# Radio.net
KiCad netlist of a schematic drawn in Altium Designer
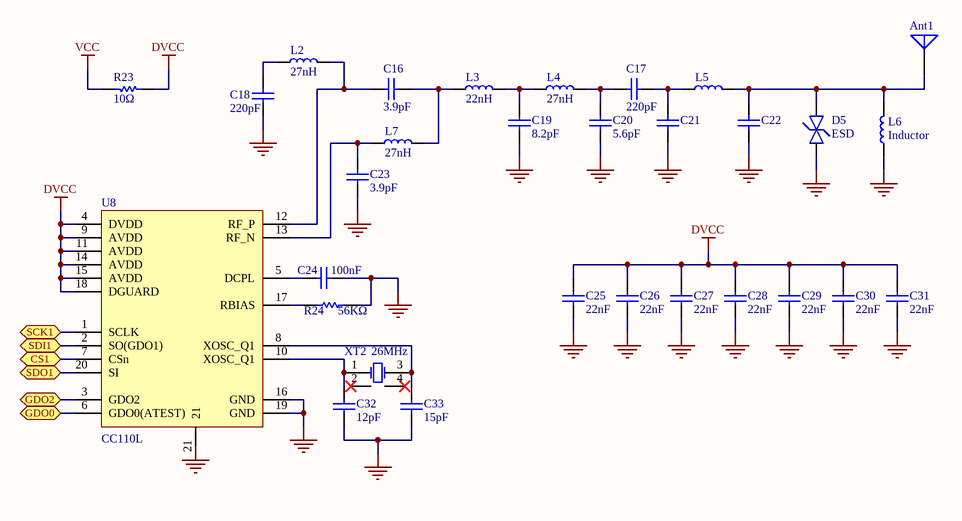
[diagram p0: Radio.SchDoc]

(export (version "E")
  (design (tool "Eeschema 10.0.6"))
  (components
    (comp (ref "Ant1")
      (value "Antenna")
      (footprint "35 mil hole")
      (description "6.8\" Whip Antenna")
      (fields (field (name "MANUFACTURER") "Alpha Wire"))
      (libsource (lib "Miscellaneous Devices") (part "Antenna"))
    )
    (comp (ref "C16")
      (value "3.9pF")
      (footprint "0402 Small")
      (description "Capacitor, 3.9p, 0402, NP0, +-0.25pF, 50V")
      (fields (field (name "MANUFACTURER") "MURATA ELECTRONICS"))
      (libsource (lib "Miscellaneous Devices") (part "Cap"))
    )
    (comp (ref "C17")
      (value "220pF")
      (footprint "0402 Small")
      (description "Capacitor, 220p, 0402, NP0, 5%, 50V")
      (fields (field (name "MANUFACTURER") "MURATA ELECTRONICS"))
      (libsource (lib "Miscellaneous Devices") (part "Cap"))
    )
    (comp (ref "C18")
      (value "220pF")
      (footprint "0402 Small")
      (description "Capacitor, 220p, 0402, NP0, 5%, 50V")
      (fields (field (name "MANUFACTURER") "MURATA ELECTRONICS"))
      (libsource (lib "Miscellaneous Devices") (part "Cap"))
    )
    (comp (ref "C19")
      (value "8.2pF")
      (footprint "0402 Small")
      (description "Capacitor, 8.2p, 0402, NP0, +-0.25pF, 50V")
      (fields (field (name "MANUFACTURER") "MURATA ELECTRONICS"))
      (libsource (lib "Miscellaneous Devices") (part "Cap"))
    )
    (comp (ref "C20")
      (value "5.6pF")
      (footprint "0402 Small")
      (description "Capacitor, 5.6p, 0402, NP0, +-0.25pF, 50V")
      (fields (field (name "MANUFACTURER") "MURATA ELECTRONICS"))
      (libsource (lib "Miscellaneous Devices") (part "Cap"))
    )
    (comp (ref "C21")
      (value "NP")
      (footprint "0402 Small")
      (libsource (lib "Miscellaneous Devices") (part "Cap"))
    )
    (comp (ref "C22")
      (value "NP")
      (footprint "0402 Small")
      (libsource (lib "Miscellaneous Devices") (part "Cap"))
    )
    (comp (ref "C23")
      (value "3.9pF")
      (footprint "0402 Small")
      (description "Capacitor, 3.9p, 0402, NP0, +-0.25pF, 50V")
      (fields (field (name "MANUFACTURER") "MURATA ELECTRONICS"))
      (libsource (lib "Miscellaneous Devices") (part "Cap"))
    )
    (comp (ref "C24")
      (value "100nF")
      (footprint "0402 Small")
      (description "Capacitor, 100n, 0402, X5R, 10%, 10V")
      (fields (field (name "MANUFACTURER") "MURATA ELECTRONICS"))
      (libsource (lib "Miscellaneous Devices") (part "Cap"))
    )
    (comp (ref "C25")
      (value "22nF")
      (footprint "0402 Small")
      (description "Capacitor, 22n, 0402, X7R, 10%, 25V")
      (fields (field (name "MANUFACTURER") "MURATA ELECTRONICS"))
      (libsource (lib "Miscellaneous Devices") (part "Cap"))
    )
    (comp (ref "C26")
      (value "22nF")
      (footprint "0402 Small")
      (description "Capacitor, 22n, 0402, X7R, 10%, 25V")
      (fields (field (name "MANUFACTURER") "MURATA ELECTRONICS"))
      (libsource (lib "Miscellaneous Devices") (part "Cap"))
    )
    (comp (ref "C27")
      (value "22nF")
      (footprint "0402 Small")
      (description "Capacitor, 22n, 0402, X7R, 10%, 25V")
      (fields (field (name "MANUFACTURER") "MURATA ELECTRONICS"))
      (libsource (lib "Miscellaneous Devices") (part "Cap"))
    )
    (comp (ref "C28")
      (value "22nF")
      (footprint "0402 Small")
      (description "Capacitor, 22n, 0402, X7R, 10%, 25V")
      (fields (field (name "MANUFACTURER") "MURATA ELECTRONICS"))
      (libsource (lib "Miscellaneous Devices") (part "Cap"))
    )
    (comp (ref "C29")
      (value "22nF")
      (footprint "0402 Small")
      (description "Capacitor, 22n, 0402, X7R, 10%, 25V")
      (fields (field (name "MANUFACTURER") "MURATA ELECTRONICS"))
      (libsource (lib "Miscellaneous Devices") (part "Cap"))
    )
    (comp (ref "C30")
      (value "22nF")
      (footprint "0402 Small")
      (description "Capacitor, 22n, 0402, X7R, 10%, 25V")
      (fields (field (name "MANUFACTURER") "MURATA ELECTRONICS"))
      (libsource (lib "Miscellaneous Devices") (part "Cap"))
    )
    (comp (ref "C31")
      (value "22nF")
      (footprint "0402 Small")
      (description "Capacitor, 22n, 0402, X7R, 10%, 25V")
      (fields (field (name "MANUFACTURER") "MURATA ELECTRONICS"))
      (libsource (lib "Miscellaneous Devices") (part "Cap"))
    )
    (comp (ref "C32")
      (value "12pF")
      (footprint "0402 Small")
      (description "CAP CER 12PF 50V 5% NP0 0402")
      (fields (field (name "MANUFACTURER") "MURATA ELECTRONICS"))
      (libsource (lib "Miscellaneous Devices") (part "Cap"))
    )
    (comp (ref "C33")
      (value "15pF")
      (footprint "0402 Small")
      (description "CAP CER 15PF 50V 5% NP0 0402")
      (fields (field (name "MANUFACTURER") "MURATA ELECTRONICS"))
      (libsource (lib "Miscellaneous Devices") (part "Cap"))
    )
    (comp (ref "D5")
      (value "ESD")
      (footprint "XDFN2")
      (description "TVS DIODE 16VWM 39VC 2XDFN")
      (fields (field (name "MANUFACTURER") "ON Semiconductor"))
      (libsource (lib "Curtis") (part "BiDi"))
    )
    (comp (ref "L2")
      (value "27nH")
      (footprint "0402 Small")
      (description "Inductor, 27n, 0402, ±5%")
      (fields (field (name "MANUFACTURER") "MURATA ELECTRONICS"))
      (libsource (lib "Curtis") (part "Inductor"))
    )
    (comp (ref "L3")
      (value "22nH")
      (footprint "0402 Small")
      (description "Inductor, 22n, 0402, ±5%")
      (fields (field (name "MANUFACTURER") "MURATA ELECTRONICS"))
      (libsource (lib "Curtis") (part "Inductor"))
    )
    (comp (ref "L4")
      (value "27nH")
      (footprint "0402 Small")
      (description "Inductor, 27n, 0402, ±5%")
      (fields (field (name "MANUFACTURER") "MURATA ELECTRONICS"))
      (libsource (lib "Curtis") (part "Inductor"))
    )
    (comp (ref "L5") (value "NP") (footprint "0402 Small") (libsource (lib "Curtis") (part "Inductor")))
    (comp (ref "L6")
      (value "Inductor")
      (footprint "0402 Small")
      (description "Fixed Inductors 0.68uH")
      (fields (field (name "MANUFACTURER") "TDK"))
      (libsource (lib "Curtis") (part "Inductor"))
    )
    (comp (ref "L7")
      (value "27nH")
      (footprint "0402 Small")
      (description "Inductor, 27n, 0402, ±5%")
      (fields (field (name "MANUFACTURER") "MURATA ELECTRONICS"))
      (libsource (lib "Curtis") (part "Inductor"))
    )
    (comp (ref "R23")
      (value "10Ω")
      (footprint "0603 Small")
      (description "Thick Film Resistors - SMD 1/10watt 10ohms 1%")
      (fields (field (name "MANUFACTURER") "Vishay Semiconductors"))
      (libsource (lib "Miscellaneous Devices") (part "Res1"))
    )
    (comp (ref "R24")
      (value "56KΩ")
      (footprint "0402 Small")
      (description "Resistor, 56k ohms, 0402,  ±1%")
      (fields (field (name "MANUFACTURER") "Koa"))
      (libsource (lib "Miscellaneous Devices") (part "Res1"))
    )
    (comp (ref "U8")
      (value "CC110L")
      (footprint "VQFN-20")
      (description "IC RF VALUE LINE TXRX 20QFN")
      (fields (field (name "MANUFACTURER") "Texas Instruments"))
      (libsource (lib "OrangeBox") (part "CC1101"))
    )
    (comp (ref "XT2")
      (value "26MHz")
      (footprint "CFPX-5")
      (description "CRYSTAL 26MHZ 10PF SMD")
      (fields (field (name "MANUFACTURER") "Suntsu"))
      (libsource (lib "Altium Design Library") (part "CRYS"))
    )
  )
  (nets
    (net (code "1") (name "/CS1") (class "Default")
      (node (ref "U8") (pin "7") (pinfunction "CSn_7") (pintype "passive"))
    )
    (net (code "2") (name "/GDO0") (class "Default")
      (node (ref "U8") (pin "6") (pinfunction "GDO0(ATEST)_6") (pintype "passive"))
    )
    (net (code "3") (name "/GDO2") (class "Default")
      (node (ref "U8") (pin "3") (pinfunction "GDO2_3") (pintype "passive"))
    )
    (net (code "4") (name "/SCK1") (class "Default")
      (node (ref "U8") (pin "1") (pinfunction "SCLK_1") (pintype "passive"))
    )
    (net (code "5") (name "/SDI1") (class "Default")
      (node (ref "U8") (pin "2") (pinfunction "SO(GDO1)_2") (pintype "passive"))
    )
    (net (code "6") (name "/SDO1") (class "Default")
      (node (ref "U8") (pin "20") (pinfunction "SI_20") (pintype "passive"))
    )
    (net (code "7") (name "DVCC") (class "Default")
      (node (ref "C25") (pin "2") (pinfunction "2_2") (pintype "passive"))
      (node (ref "C26") (pin "2") (pinfunction "2_2") (pintype "passive"))
      (node (ref "C27") (pin "2") (pinfunction "2_2") (pintype "passive"))
      (node (ref "C28") (pin "2") (pinfunction "2_2") (pintype "passive"))
      (node (ref "C29") (pin "2") (pinfunction "2_2") (pintype "passive"))
      (node (ref "C30") (pin "2") (pinfunction "2_2") (pintype "passive"))
      (node (ref "C31") (pin "2") (pinfunction "2_2") (pintype "passive"))
      (node (ref "R23") (pin "2") (pinfunction "2_2") (pintype "passive"))
      (node (ref "U8") (pin "11") (pinfunction "AVDD_11") (pintype "passive"))
      (node (ref "U8") (pin "14") (pinfunction "AVDD_14") (pintype "passive"))
      (node (ref "U8") (pin "15") (pinfunction "AVDD_15") (pintype "passive"))
      (node (ref "U8") (pin "18") (pinfunction "DGUARD_18") (pintype "passive"))
      (node (ref "U8") (pin "4") (pinfunction "DVDD_4") (pintype "passive"))
      (node (ref "U8") (pin "9") (pinfunction "AVDD_9") (pintype "passive"))
    )
    (net (code "8") (name "GND") (class "Default")
      (node (ref "C18") (pin "1") (pinfunction "1_1") (pintype "passive"))
      (node (ref "C19") (pin "2") (pinfunction "2_2") (pintype "passive"))
      (node (ref "C20") (pin "2") (pinfunction "2_2") (pintype "passive"))
      (node (ref "C21") (pin "2") (pinfunction "2_2") (pintype "passive"))
      (node (ref "C22") (pin "2") (pinfunction "2_2") (pintype "passive"))
      (node (ref "C23") (pin "2") (pinfunction "2_2") (pintype "passive"))
      (node (ref "C24") (pin "1") (pinfunction "1_1") (pintype "passive"))
      (node (ref "C25") (pin "1") (pinfunction "1_1") (pintype "passive"))
      (node (ref "C26") (pin "1") (pinfunction "1_1") (pintype "passive"))
      (node (ref "C27") (pin "1") (pinfunction "1_1") (pintype "passive"))
      (node (ref "C28") (pin "1") (pinfunction "1_1") (pintype "passive"))
      (node (ref "C29") (pin "1") (pinfunction "1_1") (pintype "passive"))
      (node (ref "C30") (pin "1") (pinfunction "1_1") (pintype "passive"))
      (node (ref "C31") (pin "1") (pinfunction "1_1") (pintype "passive"))
      (node (ref "C32") (pin "1") (pinfunction "1_1") (pintype "passive"))
      (node (ref "C33") (pin "1") (pinfunction "1_1") (pintype "passive"))
      (node (ref "D5") (pin "1") (pinfunction "1_1") (pintype "passive"))
      (node (ref "L6") (pin "1") (pinfunction "1_1") (pintype "passive"))
      (node (ref "R24") (pin "2") (pinfunction "2_2") (pintype "passive"))
      (node (ref "U8") (pin "16") (pinfunction "GND_16") (pintype "passive"))
      (node (ref "U8") (pin "19") (pinfunction "GND_19") (pintype "passive"))
      (node (ref "U8") (pin "21") (pinfunction "21_21") (pintype "passive"))
    )
    (net (code "9") (name "Net-(Ant1-A)") (class "Default")
      (node (ref "Ant1") (pin "1") (pinfunction "A_1") (pintype "passive"))
      (node (ref "C22") (pin "1") (pinfunction "1_1") (pintype "passive"))
      (node (ref "D5") (pin "2") (pinfunction "2_2") (pintype "passive"))
      (node (ref "L5") (pin "2") (pinfunction "2_2") (pintype "passive"))
      (node (ref "L6") (pin "2") (pinfunction "2_2") (pintype "passive"))
    )
    (net (code "10") (name "Net-(C16-Pad1)") (class "Default")
      (node (ref "C16") (pin "1") (pinfunction "1_1") (pintype "passive"))
      (node (ref "L3") (pin "1") (pinfunction "1_1") (pintype "passive"))
      (node (ref "L7") (pin "2") (pinfunction "2_2") (pintype "passive"))
    )
    (net (code "11") (name "Net-(C17-Pad1)") (class "Default")
      (node (ref "C17") (pin "1") (pinfunction "1_1") (pintype "passive"))
      (node (ref "C20") (pin "1") (pinfunction "1_1") (pintype "passive"))
      (node (ref "L4") (pin "2") (pinfunction "2_2") (pintype "passive"))
    )
    (net (code "12") (name "Net-(C17-Pad2)") (class "Default")
      (node (ref "C17") (pin "2") (pinfunction "2_2") (pintype "passive"))
      (node (ref "C21") (pin "1") (pinfunction "1_1") (pintype "passive"))
      (node (ref "L5") (pin "1") (pinfunction "1_1") (pintype "passive"))
    )
    (net (code "13") (name "Net-(C18-Pad2)") (class "Default")
      (node (ref "C18") (pin "2") (pinfunction "2_2") (pintype "passive"))
      (node (ref "L2") (pin "1") (pinfunction "1_1") (pintype "passive"))
    )
    (net (code "14") (name "Net-(C19-Pad1)") (class "Default")
      (node (ref "C19") (pin "1") (pinfunction "1_1") (pintype "passive"))
      (node (ref "L3") (pin "2") (pinfunction "2_2") (pintype "passive"))
      (node (ref "L4") (pin "1") (pinfunction "1_1") (pintype "passive"))
    )
    (net (code "15") (name "Net-(C33-Pad2)") (class "Default")
      (node (ref "C33") (pin "2") (pinfunction "2_2") (pintype "passive"))
      (node (ref "U8") (pin "8") (pinfunction "XOSC_Q1_8") (pintype "passive"))
      (node (ref "XT2") (pin "3") (pinfunction "3_3") (pintype "passive"))
    )
    (net (code "16") (name "Net-(U8-DCPL)") (class "Default")
      (node (ref "C24") (pin "2") (pinfunction "2_2") (pintype "passive"))
      (node (ref "U8") (pin "5") (pinfunction "DCPL_5") (pintype "passive"))
    )
    (net (code "17") (name "Net-(U8-RBIAS)") (class "Default")
      (node (ref "R24") (pin "1") (pinfunction "1_1") (pintype "passive"))
      (node (ref "U8") (pin "17") (pinfunction "RBIAS_17") (pintype "passive"))
    )
    (net (code "18") (name "Net-(U8-RF_N)") (class "Default")
      (node (ref "C23") (pin "1") (pinfunction "1_1") (pintype "passive"))
      (node (ref "L7") (pin "1") (pinfunction "1_1") (pintype "passive"))
      (node (ref "U8") (pin "13") (pinfunction "RF_N_13") (pintype "passive"))
    )
    (net (code "19") (name "Net-(U8-RF_P)") (class "Default")
      (node (ref "C16") (pin "2") (pinfunction "2_2") (pintype "passive"))
      (node (ref "L2") (pin "2") (pinfunction "2_2") (pintype "passive"))
      (node (ref "U8") (pin "12") (pinfunction "RF_P_12") (pintype "passive"))
    )
    (net (code "20") (name "Net-(XT2-OSC1)") (class "Default")
      (node (ref "C32") (pin "2") (pinfunction "2_2") (pintype "passive"))
      (node (ref "U8") (pin "10") (pinfunction "XOSC_Q1_10") (pintype "passive"))
      (node (ref "XT2") (pin "1") (pinfunction "OSC1_1") (pintype "passive"))
    )
    (net (code "21") (name "VCC") (class "Default")
      (node (ref "R23") (pin "1") (pinfunction "1_1") (pintype "passive"))
    )
    (net (code "22") (name "unconnected-(XT2-OSC2-Pad2)") (class "Default")
      (node (ref "XT2") (pin "2") (pinfunction "OSC2_2") (pintype "passive+no_connect"))
    )
    (net (code "23") (name "unconnected-(XT2-Pad4)") (class "Default")
      (node (ref "XT2") (pin "4") (pinfunction "4_4") (pintype "passive+no_connect"))
    )
  )
)
